# touch_board.net
KiCad netlist of a schematic drawn in EAGLE
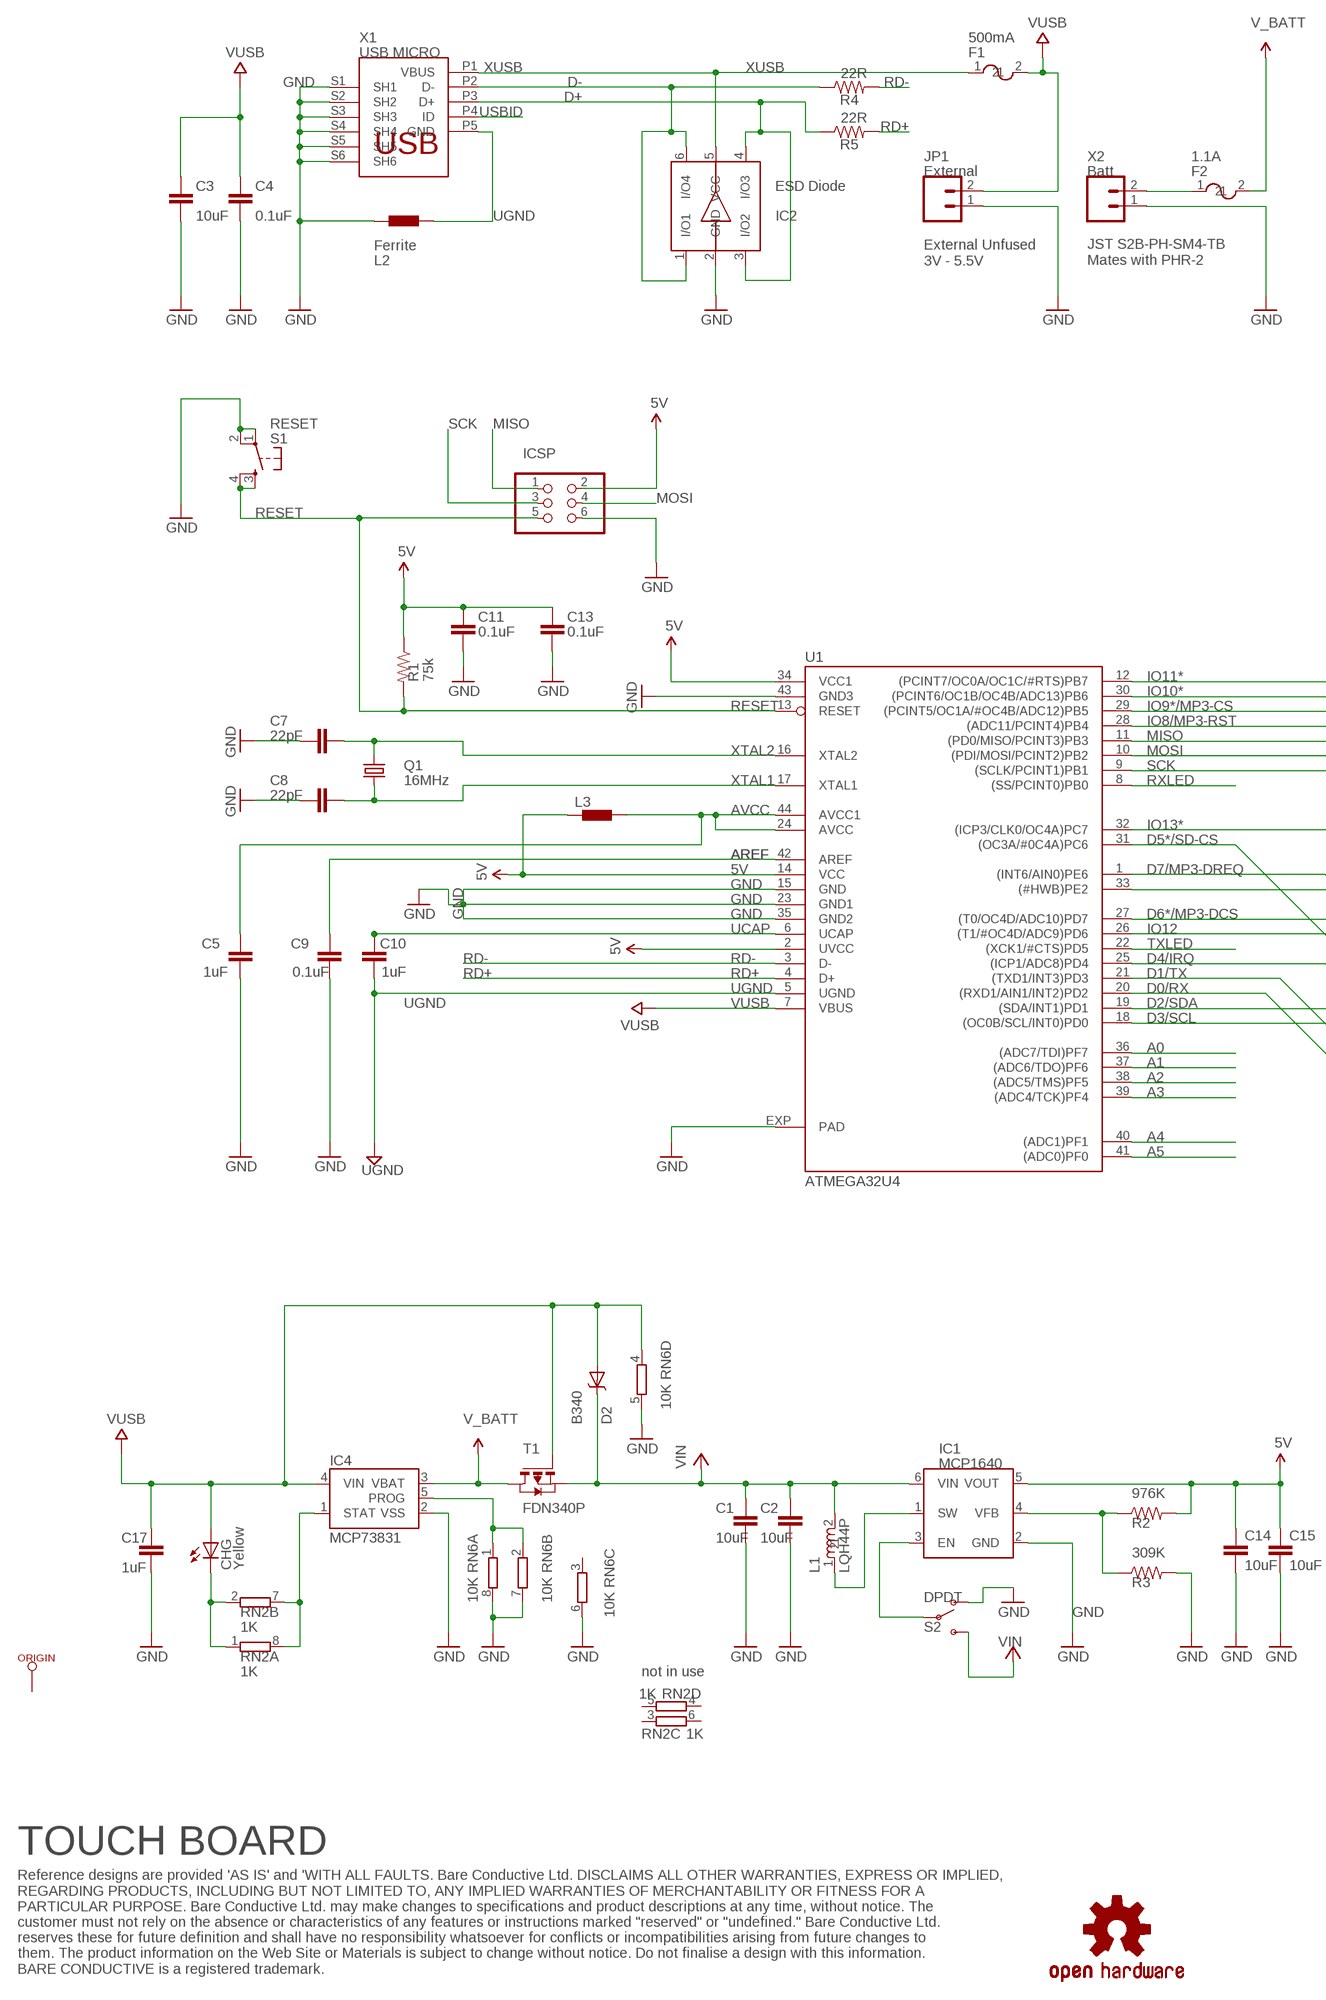
[diagram p0: schematic, sheet 1, part 1 of 2]
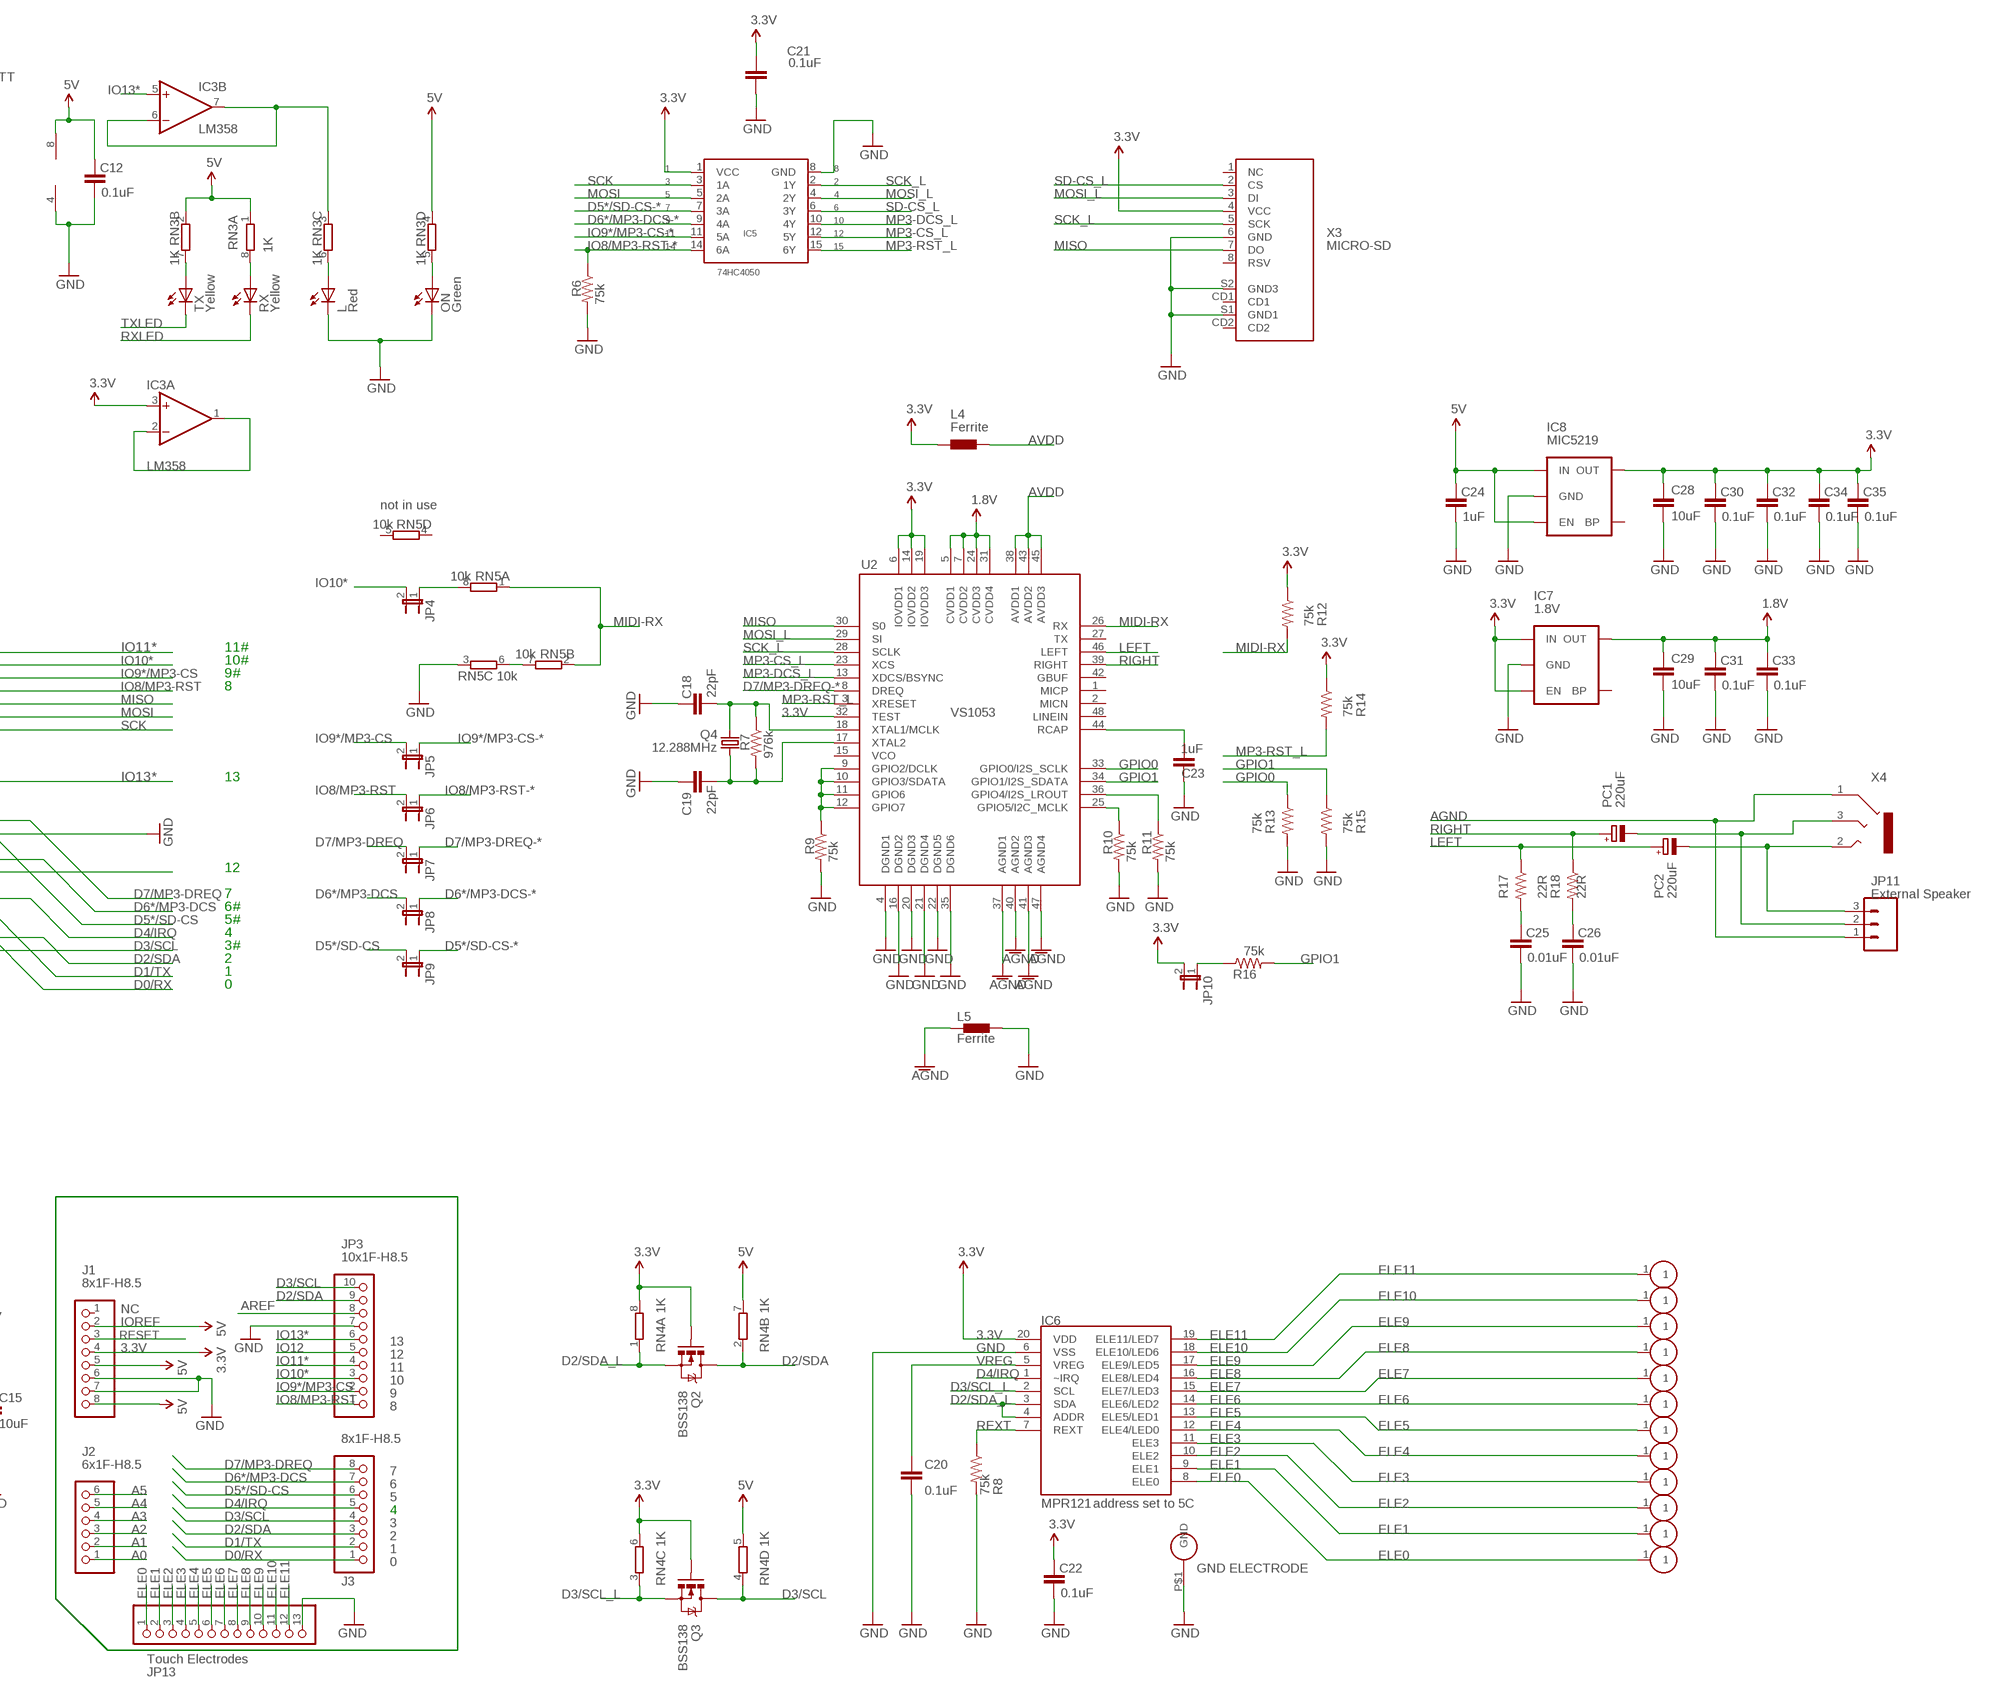
[diagram p1: schematic, sheet 1, part 2 of 2]

(export (version "E")
  (design (tool "Eeschema 10.0.6"))
  (components
    (comp (ref "C1")
      (value "10uF")
      (footprint "eagle-import:1206")
      (libsource (lib "eagle-import") (part "SparkFun-Capacitors_CAP1206"))
    )
    (comp (ref "C2")
      (value "10uF")
      (footprint "eagle-import:1206")
      (libsource (lib "eagle-import") (part "SparkFun-Capacitors_CAP1206"))
    )
    (comp (ref "C3")
      (value "10uF")
      (footprint "eagle-import:1206")
      (libsource (lib "eagle-import") (part "SparkFun-Capacitors_CAP1206"))
    )
    (comp (ref "C4")
      (value "0.1uF")
      (footprint "eagle-import:0402-CAP")
      (libsource (lib "eagle-import") (part "CAP0402-CAP"))
    )
    (comp (ref "C5")
      (value "1uF")
      (footprint "eagle-import:0402-CAP")
      (libsource (lib "eagle-import") (part "CAP0402-CAP"))
    )
    (comp (ref "C7")
      (value "22pF")
      (footprint "eagle-import:0402-CAP")
      (libsource (lib "eagle-import") (part "CAP0402-CAP"))
    )
    (comp (ref "C8")
      (value "22pF")
      (footprint "eagle-import:0402-CAP")
      (libsource (lib "eagle-import") (part "CAP0402-CAP"))
    )
    (comp (ref "C9")
      (value "0.1uF")
      (footprint "eagle-import:0402-CAP")
      (libsource (lib "eagle-import") (part "CAP0402-CAP"))
    )
    (comp (ref "C10")
      (value "1uF")
      (footprint "eagle-import:0402-CAP")
      (libsource (lib "eagle-import") (part "CAP0402-CAP"))
    )
    (comp (ref "C11")
      (value "0.1uF")
      (footprint "eagle-import:0402-CAP")
      (libsource (lib "eagle-import") (part "CAP0402-CAP"))
    )
    (comp (ref "C12")
      (value "0.1uF")
      (footprint "eagle-import:0402-CAP")
      (libsource (lib "eagle-import") (part "CAP0402-CAP"))
    )
    (comp (ref "C13")
      (value "0.1uF")
      (footprint "eagle-import:0402-CAP")
      (libsource (lib "eagle-import") (part "CAP0402-CAP"))
    )
    (comp (ref "C14")
      (value "10uF")
      (footprint "eagle-import:1206")
      (libsource (lib "eagle-import") (part "SparkFun-Capacitors_CAP1206"))
    )
    (comp (ref "C15")
      (value "10uF")
      (footprint "eagle-import:1206")
      (libsource (lib "eagle-import") (part "SparkFun-Capacitors_CAP1206"))
    )
    (comp (ref "C17")
      (value "1uF")
      (footprint "eagle-import:0402-CAP")
      (libsource (lib "eagle-import") (part "CAP0402-CAP"))
    )
    (comp (ref "C18")
      (value "22pF")
      (footprint "eagle-import:0402-CAP")
      (libsource (lib "eagle-import") (part "CAP0402-CAP"))
    )
    (comp (ref "C19")
      (value "22pF")
      (footprint "eagle-import:0402-CAP")
      (libsource (lib "eagle-import") (part "CAP0402-CAP"))
    )
    (comp (ref "C20")
      (value "0.1uF")
      (footprint "eagle-import:0402-CAP")
      (libsource (lib "eagle-import") (part "CAP0402-CAP"))
    )
    (comp (ref "C21")
      (value "0.1uF")
      (footprint "eagle-import:0402-CAP")
      (libsource (lib "eagle-import") (part "CAP0402-CAP"))
    )
    (comp (ref "C22")
      (value "0.1uF")
      (footprint "eagle-import:0402-CAP")
      (libsource (lib "eagle-import") (part "CAP0402-CAP"))
    )
    (comp (ref "C23")
      (value "1uF")
      (footprint "eagle-import:0402-CAP")
      (libsource (lib "eagle-import") (part "CAP0402-CAP"))
    )
    (comp (ref "C24")
      (value "1uF")
      (footprint "eagle-import:0402-CAP")
      (libsource (lib "eagle-import") (part "CAP0402-CAP"))
    )
    (comp (ref "C25")
      (value "0.01uF")
      (footprint "eagle-import:0402-CAP")
      (libsource (lib "eagle-import") (part "CAP0402-CAP"))
    )
    (comp (ref "C26")
      (value "0.01uF")
      (footprint "eagle-import:0402-CAP")
      (libsource (lib "eagle-import") (part "CAP0402-CAP"))
    )
    (comp (ref "C28")
      (value "10uF")
      (footprint "eagle-import:1206")
      (libsource (lib "eagle-import") (part "SparkFun-Capacitors_CAP1206"))
    )
    (comp (ref "C29")
      (value "10uF")
      (footprint "eagle-import:1206")
      (libsource (lib "eagle-import") (part "SparkFun-Capacitors_CAP1206"))
    )
    (comp (ref "C30")
      (value "0.1uF")
      (footprint "eagle-import:0402-CAP")
      (libsource (lib "eagle-import") (part "CAP0402-CAP"))
    )
    (comp (ref "C31")
      (value "0.1uF")
      (footprint "eagle-import:0402-CAP")
      (libsource (lib "eagle-import") (part "CAP0402-CAP"))
    )
    (comp (ref "C32")
      (value "0.1uF")
      (footprint "eagle-import:0402-CAP")
      (libsource (lib "eagle-import") (part "CAP0402-CAP"))
    )
    (comp (ref "C33")
      (value "0.1uF")
      (footprint "eagle-import:0402-CAP")
      (libsource (lib "eagle-import") (part "CAP0402-CAP"))
    )
    (comp (ref "C34")
      (value "0.1uF")
      (footprint "eagle-import:0402-CAP")
      (libsource (lib "eagle-import") (part "CAP0402-CAP"))
    )
    (comp (ref "C35")
      (value "0.1uF")
      (footprint "eagle-import:0402-CAP")
      (libsource (lib "eagle-import") (part "CAP0402-CAP"))
    )
    (comp (ref "CHG")
      (value "Yellow")
      (footprint "eagle-import:CHIPLED_0805")
      (libsource (lib "eagle-import") (part "LEDCHIPLED_0805"))
    )
    (comp (ref "D2")
      (value "B340")
      (footprint "eagle-import:SMA-DIODE")
      (libsource (lib "eagle-import") (part "DIODE-SCHOTTKY_"))
    )
    (comp (ref "F1")
      (value "500mA")
      (footprint "eagle-import:0805")
      (libsource (lib "eagle-import") (part "PTC"))
    )
    (comp (ref "F2")
      (value "1.1A")
      (footprint "eagle-import:0805")
      (libsource (lib "eagle-import") (part "PTC"))
    )
    (comp (ref "IC1")
      (value "MCP1640")
      (footprint "eagle-import:6-LEAD-SOT23")
      (libsource (lib "eagle-import") (part "BOOST-REG"))
    )
    (comp (ref "IC2")
      (value "ESD Diode")
      (footprint "eagle-import:SOT457")
      (libsource (lib "eagle-import") (part "PRTR5V"))
    )
    (comp (ref "IC3")
      (value "LM358")
      (footprint "eagle-import:MSOP08")
      (libsource (lib "eagle-import") (part "LMV358?MMX"))
    )
    (comp (ref "IC4")
      (value "MCP73831")
      (footprint "eagle-import:SOT23-5")
      (libsource (lib "eagle-import") (part "MCP73831"))
    )
    (comp (ref "IC5")
      (value "74HC4050")
      (footprint "eagle-import:TSSOP-16")
      (libsource (lib "eagle-import") (part "74HC4050PW"))
    )
    (comp (ref "IC6")
      (value "MPR121")
      (footprint "eagle-import:QFN-20-0.4MM")
      (libsource (lib "eagle-import") (part "MPR121QFN20"))
    )
    (comp (ref "IC7")
      (value "1.8V")
      (footprint "eagle-import:SC70")
      (libsource (lib "eagle-import") (part "V_REG_LDOSMD2"))
    )
    (comp (ref "IC8")
      (value "MIC5219")
      (footprint "eagle-import:SOT23-5")
      (libsource (lib "eagle-import") (part "V_REG_LDOSMD"))
    )
    (comp (ref "ICSP")
      (value "ICSP")
      (footprint "eagle-import:2X03")
      (libsource (lib "eagle-import") (part "PINHD-2X3"))
    )
    (comp (ref "J1")
      (value "8x1F-H8.5")
      (footprint "eagle-import:1X08")
      (libsource (lib "eagle-import") (part "PINHD-1X8"))
    )
    (comp (ref "J2")
      (value "6x1F-H8.5")
      (footprint "eagle-import:1X06")
      (libsource (lib "eagle-import") (part "PINHD-1X6"))
    )
    (comp (ref "J3")
      (value "8x1F-H8.5")
      (footprint "eagle-import:1X08")
      (libsource (lib "eagle-import") (part "PINHD-1X8"))
    )
    (comp (ref "JP1")
      (value "External")
      (footprint "eagle-import:1X02")
      (libsource (lib "eagle-import") (part "M02PTH"))
    )
    (comp (ref "JP3")
      (value "10x1F-H8.5")
      (footprint "eagle-import:1X10")
      (libsource (lib "eagle-import") (part "PINHD-1X10"))
    )
    (comp (ref "JP4")
      (value "JUMPER-2SMD-NO")
      (footprint "eagle-import:SJ_2S-NO")
      (libsource (lib "eagle-import") (part "JUMPER-2SMD-NO"))
    )
    (comp (ref "JP5")
      (value "JUMPER-2SMD-NC")
      (footprint "eagle-import:SJ_2S")
      (libsource (lib "eagle-import") (part "JUMPER-2SMD-NC"))
    )
    (comp (ref "JP6")
      (value "JUMPER-2SMD-NC")
      (footprint "eagle-import:SJ_2S")
      (libsource (lib "eagle-import") (part "JUMPER-2SMD-NC"))
    )
    (comp (ref "JP7")
      (value "JUMPER-2SMD-NC")
      (footprint "eagle-import:SJ_2S")
      (libsource (lib "eagle-import") (part "JUMPER-2SMD-NC"))
    )
    (comp (ref "JP8")
      (value "JUMPER-2SMD-NC")
      (footprint "eagle-import:SJ_2S")
      (libsource (lib "eagle-import") (part "JUMPER-2SMD-NC"))
    )
    (comp (ref "JP9")
      (value "JUMPER-2SMD-NC")
      (footprint "eagle-import:SJ_2S")
      (libsource (lib "eagle-import") (part "JUMPER-2SMD-NC"))
    )
    (comp (ref "JP10")
      (value "JUMPER-2SMD-NO")
      (footprint "eagle-import:SJ_2S-NO")
      (libsource (lib "eagle-import") (part "JUMPER-2SMD-NO"))
    )
    (comp (ref "JP11")
      (value "External Speaker")
      (footprint "eagle-import:1X03")
      (libsource (lib "eagle-import") (part "M03PTH"))
    )
    (comp (ref "JP13")
      (value "Touch Electrodes")
      (footprint "eagle-import:1X13")
      (libsource (lib "eagle-import") (part "PINHD-1X13"))
    )
    (comp (ref "L")
      (value "Red")
      (footprint "eagle-import:CHIPLED_0805")
      (libsource (lib "eagle-import") (part "LEDCHIPLED_0805"))
    )
    (comp (ref "L1")
      (value "LQH44P")
      (footprint "eagle-import:LQH44PN100MP0L")
      (libsource (lib "eagle-import") (part "LQH44P"))
    )
    (comp (ref "L2")
      (value "Ferrite")
      (footprint "eagle-import:0402")
      (libsource (lib "eagle-import") (part "BLM15HB121SN1"))
    )
    (comp (ref "L3")
      (value "BLM15HB121SN1")
      (footprint "eagle-import:0402")
      (libsource (lib "eagle-import") (part "BLM15HB121SN1"))
    )
    (comp (ref "L4")
      (value "Ferrite")
      (footprint "eagle-import:0402")
      (libsource (lib "eagle-import") (part "BLM15HB121SN1"))
    )
    (comp (ref "L5")
      (value "Ferrite")
      (footprint "eagle-import:0402")
      (libsource (lib "eagle-import") (part "BLM15HB121SN1"))
    )
    (comp (ref "ON")
      (value "Green")
      (footprint "eagle-import:CHIPLED_0805")
      (libsource (lib "eagle-import") (part "LEDCHIPLED_0805"))
    )
    (comp (ref "ORIGIN")
      (value "TP_SP")
      (footprint "eagle-import:TP-SP")
      (libsource (lib "eagle-import") (part "TP_SP"))
    )
    (comp (ref "PC1")
      (value "220uF")
      (footprint "eagle-import:PANASONIC_D")
      (libsource (lib "eagle-import") (part "CPOL-EUD"))
    )
    (comp (ref "PC2")
      (value "220uF")
      (footprint "eagle-import:PANASONIC_D")
      (libsource (lib "eagle-import") (part "CPOL-EUD"))
    )
    (comp (ref "Q1")
      (value "16MHz")
      (footprint "eagle-import:CRYSTAL-SMD-5X3")
      (libsource (lib "eagle-import") (part "CRYSTAL5X3"))
    )
    (comp (ref "Q2")
      (value "BSS138")
      (footprint "eagle-import:SOT23-3")
      (libsource (lib "eagle-import") (part "MOSFET-NCHANNELSMD"))
    )
    (comp (ref "Q3")
      (value "BSS138")
      (footprint "eagle-import:SOT23-3")
      (libsource (lib "eagle-import") (part "MOSFET-NCHANNELSMD"))
    )
    (comp (ref "Q4")
      (value "12.288MHz")
      (footprint "eagle-import:CRYSTAL-SMD-5X3")
      (libsource (lib "eagle-import") (part "CRYSTAL5X3"))
    )
    (comp (ref "R1")
      (value "75k")
      (footprint "eagle-import:0402-RES")
      (libsource (lib "eagle-import") (part "RESISTOR0402-RES"))
    )
    (comp (ref "R2")
      (value "976K")
      (footprint "eagle-import:0402-RES")
      (libsource (lib "eagle-import") (part "RESISTOR0402-RES"))
    )
    (comp (ref "R3")
      (value "309K")
      (footprint "eagle-import:0402-RES")
      (libsource (lib "eagle-import") (part "RESISTOR0402-RES"))
    )
    (comp (ref "R4")
      (value "22R")
      (footprint "eagle-import:0402-RES")
      (libsource (lib "eagle-import") (part "RESISTOR0402-RES"))
    )
    (comp (ref "R5")
      (value "22R")
      (footprint "eagle-import:0402-RES")
      (libsource (lib "eagle-import") (part "RESISTOR0402-RES"))
    )
    (comp (ref "R6")
      (value "75k")
      (footprint "eagle-import:0402-RES")
      (libsource (lib "eagle-import") (part "RESISTOR0402-RES"))
    )
    (comp (ref "R7")
      (value "976k")
      (footprint "eagle-import:0402-RES")
      (libsource (lib "eagle-import") (part "RESISTOR0402-RES"))
    )
    (comp (ref "R8")
      (value "75k")
      (footprint "eagle-import:0402-RES")
      (libsource (lib "eagle-import") (part "RESISTOR0402-RES"))
    )
    (comp (ref "R9")
      (value "75k")
      (footprint "eagle-import:0402-RES")
      (libsource (lib "eagle-import") (part "RESISTOR0402-RES"))
    )
    (comp (ref "R10")
      (value "75k")
      (footprint "eagle-import:0402-RES")
      (libsource (lib "eagle-import") (part "RESISTOR0402-RES"))
    )
    (comp (ref "R11")
      (value "75k")
      (footprint "eagle-import:0402-RES")
      (libsource (lib "eagle-import") (part "RESISTOR0402-RES"))
    )
    (comp (ref "R12")
      (value "75k")
      (footprint "eagle-import:0402-RES")
      (libsource (lib "eagle-import") (part "RESISTOR0402-RES"))
    )
    (comp (ref "R13")
      (value "75k")
      (footprint "eagle-import:0402-RES")
      (libsource (lib "eagle-import") (part "RESISTOR0402-RES"))
    )
    (comp (ref "R14")
      (value "75k")
      (footprint "eagle-import:0402-RES")
      (libsource (lib "eagle-import") (part "RESISTOR0402-RES"))
    )
    (comp (ref "R15")
      (value "75k")
      (footprint "eagle-import:0402-RES")
      (libsource (lib "eagle-import") (part "RESISTOR0402-RES"))
    )
    (comp (ref "R16")
      (value "75k")
      (footprint "eagle-import:0402-RES")
      (libsource (lib "eagle-import") (part "RESISTOR0402-RES"))
    )
    (comp (ref "R17")
      (value "22R")
      (footprint "eagle-import:0402-RES")
      (libsource (lib "eagle-import") (part "RESISTOR0402-RES"))
    )
    (comp (ref "R18")
      (value "22R")
      (footprint "eagle-import:0402-RES")
      (libsource (lib "eagle-import") (part "RESISTOR0402-RES"))
    )
    (comp (ref "RN2")
      (value "1K")
      (footprint "eagle-import:CAY16")
      (libsource (lib "eagle-import") (part "4R-NCAY16"))
    )
    (comp (ref "RN3")
      (value "1K")
      (footprint "eagle-import:CAY16")
      (libsource (lib "eagle-import") (part "4R-NCAY16"))
    )
    (comp (ref "RN4")
      (value "1K")
      (footprint "eagle-import:CAY16")
      (libsource (lib "eagle-import") (part "4R-NCAY16"))
    )
    (comp (ref "RN5")
      (value "10k")
      (footprint "eagle-import:CAY16")
      (libsource (lib "eagle-import") (part "4R-NCAY16"))
    )
    (comp (ref "RN6")
      (value "10K")
      (footprint "eagle-import:CAY16")
      (libsource (lib "eagle-import") (part "4R-NCAY16"))
    )
    (comp (ref "RX")
      (value "Yellow")
      (footprint "eagle-import:CHIPLED_0805")
      (libsource (lib "eagle-import") (part "LEDCHIPLED_0805"))
    )
    (comp (ref "S1")
      (value "RESET")
      (footprint "eagle-import:TACTILE_SWITCH_SMD@1")
      (libsource (lib "eagle-import") (part "TAC_SWITCHSND"))
    )
    (comp (ref "S2")
      (value "DPDT")
      (footprint "eagle-import:JS202011SCQN")
      (libsource (lib "eagle-import") (part "DPDT-SWITCH"))
    )
    (comp (ref "T1")
      (value "FDN340P")
      (footprint "eagle-import:SOT-23")
      (libsource (lib "eagle-import") (part "PMOSSOT23"))
    )
    (comp (ref "TX")
      (value "Yellow")
      (footprint "eagle-import:CHIPLED_0805")
      (libsource (lib "eagle-import") (part "LEDCHIPLED_0805"))
    )
    (comp (ref "U$1")
      (value "EDGE-ELEC-LEFT")
      (footprint "eagle-import:EDGE-ELEC-LEFT")
      (libsource (lib "eagle-import") (part "EDGE-ELEC-LEFT"))
    )
    (comp (ref "U$3")
      (value "EDGE-ELEC-RIGHT")
      (footprint "eagle-import:EDGE-ELEC-RIGHT")
      (libsource (lib "eagle-import") (part "EDGE-ELEC-RIGHT"))
    )
    (comp (ref "U$6")
      (value "EDGE-GND")
      (footprint "eagle-import:EDGE-GND")
      (libsource (lib "eagle-import") (part "EDGE-GND"))
    )
    (comp (ref "U$8")
      (value "OSHW-LOGO")
      (footprint "eagle-import:OSHW-LOGO")
      (libsource (lib "eagle-import") (part "OSHW-LOGO"))
    )
    (comp (ref "U$17")
      (value "EDGE-ELEC")
      (footprint "eagle-import:EDGE-ELEC")
      (libsource (lib "eagle-import") (part "EDGE-ELEC"))
    )
    (comp (ref "U$18")
      (value "EDGE-ELEC")
      (footprint "eagle-import:EDGE-ELEC")
      (libsource (lib "eagle-import") (part "EDGE-ELEC"))
    )
    (comp (ref "U$22")
      (value "EDGE-ELEC")
      (footprint "eagle-import:EDGE-ELEC")
      (libsource (lib "eagle-import") (part "EDGE-ELEC"))
    )
    (comp (ref "U$24")
      (value "EDGE-ELEC")
      (footprint "eagle-import:EDGE-ELEC")
      (libsource (lib "eagle-import") (part "EDGE-ELEC"))
    )
    (comp (ref "U$26")
      (value "EDGE-ELEC")
      (footprint "eagle-import:EDGE-ELEC")
      (libsource (lib "eagle-import") (part "EDGE-ELEC"))
    )
    (comp (ref "U$27")
      (value "EDGE-ELEC")
      (footprint "eagle-import:EDGE-ELEC")
      (libsource (lib "eagle-import") (part "EDGE-ELEC"))
    )
    (comp (ref "U$28")
      (value "EDGE-ELEC")
      (footprint "eagle-import:EDGE-ELEC")
      (libsource (lib "eagle-import") (part "EDGE-ELEC"))
    )
    (comp (ref "U$29")
      (value "EDGE-ELEC")
      (footprint "eagle-import:EDGE-ELEC")
      (libsource (lib "eagle-import") (part "EDGE-ELEC"))
    )
    (comp (ref "U$30")
      (value "EDGE-ELEC")
      (footprint "eagle-import:EDGE-ELEC")
      (libsource (lib "eagle-import") (part "EDGE-ELEC"))
    )
    (comp (ref "U$31")
      (value "EDGE-ELEC")
      (footprint "eagle-import:EDGE-ELEC")
      (libsource (lib "eagle-import") (part "EDGE-ELEC"))
    )
    (comp (ref "U1")
      (value "ATMEGA32U4")
      (footprint "eagle-import:QFN44ML7X7")
      (libsource (lib "eagle-import") (part "ATMEGA32U4-XUMU"))
    )
    (comp (ref "U2")
      (value "VS1053")
      (footprint "eagle-import:LQFP-48")
      (libsource (lib "eagle-import") (part "VS1033"))
    )
    (comp (ref "X1")
      (value "USB MICRO")
      (footprint "eagle-import:CON2_USB_MICRO_B_AT")
      (libsource (lib "eagle-import") (part "MYCON2_USB-MINI-B"))
    )
    (comp (ref "X2")
      (value "Batt")
      (footprint "eagle-import:JST-2-SMD")
      (libsource (lib "eagle-import") (part "M02-JST-2MM-SMT"))
    )
    (comp (ref "X3")
      (value "MICRO-SD")
      (footprint "eagle-import:MSDC-PP-02")
      (libsource (lib "eagle-import") (part "TOBY-SD"))
    )
    (comp (ref "X4")
      (value "SJ-3523")
      (footprint "eagle-import:3POLE-JACK")
      (libsource (lib "eagle-import") (part "SJ-3523"))
    )
  )
  (nets
    (net (code "1") (name "/A0") (class "Default")
      (node (ref "J2") (pin "1") (pinfunction "1_1") (pintype "passive"))
      (node (ref "U1") (pin "36") (pinfunction "(ADC7/TDI)PF7_36") (pintype "bidirectional"))
    )
    (net (code "2") (name "/A1") (class "Default")
      (node (ref "J2") (pin "2") (pinfunction "2_2") (pintype "passive"))
      (node (ref "U1") (pin "37") (pinfunction "(ADC6/TDO)PF6_37") (pintype "bidirectional"))
    )
    (net (code "3") (name "/A2") (class "Default")
      (node (ref "J2") (pin "3") (pinfunction "3_3") (pintype "passive"))
      (node (ref "U1") (pin "38") (pinfunction "(ADC5/TMS)PF5_38") (pintype "bidirectional"))
    )
    (net (code "4") (name "/A3") (class "Default")
      (node (ref "J2") (pin "4") (pinfunction "4_4") (pintype "passive"))
      (node (ref "U1") (pin "39") (pinfunction "(ADC4/TCK)PF4_39") (pintype "bidirectional"))
    )
    (net (code "5") (name "/A4") (class "Default")
      (node (ref "J2") (pin "5") (pinfunction "5_5") (pintype "passive"))
      (node (ref "U1") (pin "40") (pinfunction "(ADC1)PF1_40") (pintype "bidirectional"))
    )
    (net (code "6") (name "/A5") (class "Default")
      (node (ref "J2") (pin "6") (pinfunction "6_6") (pintype "passive"))
      (node (ref "U1") (pin "41") (pinfunction "(ADC0)PF0_41") (pintype "bidirectional"))
    )
    (net (code "7") (name "/AREF") (class "Default")
      (node (ref "C9") (pin "2") (pinfunction "2_2") (pintype "passive"))
      (node (ref "JP3") (pin "8") (pinfunction "8_8") (pintype "passive"))
      (node (ref "U1") (pin "42") (pinfunction "AREF_42") (pintype "power_in"))
    )
    (net (code "8") (name "/AVCC") (class "Default")
      (node (ref "C5") (pin "2") (pinfunction "2_2") (pintype "passive"))
      (node (ref "L3") (pin "2") (pinfunction "2_2") (pintype "passive"))
      (node (ref "U1") (pin "24") (pinfunction "AVCC_24") (pintype "power_in"))
      (node (ref "U1") (pin "44") (pinfunction "AVCC1_44") (pintype "power_in"))
    )
    (net (code "9") (name "/AVDD") (class "Default")
      (node (ref "L4") (pin "2") (pinfunction "2_2") (pintype "passive"))
      (node (ref "U2") (pin "38") (pinfunction "AVDD1_38") (pintype "bidirectional"))
      (node (ref "U2") (pin "43") (pinfunction "AVDD2_43") (pintype "bidirectional"))
      (node (ref "U2") (pin "45") (pinfunction "AVDD3_45") (pintype "bidirectional"))
    )
    (net (code "10") (name "/D+") (class "Default")
      (node (ref "IC2") (pin "3") (pinfunction "I/O2_3") (pintype "bidirectional"))
      (node (ref "IC2") (pin "4") (pinfunction "I/O3_4") (pintype "bidirectional"))
      (node (ref "R5") (pin "1") (pinfunction "1_1") (pintype "passive"))
      (node (ref "X1") (pin "P3") (pinfunction "D+_P3") (pintype "bidirectional"))
    )
    (net (code "11") (name "/D-") (class "Default")
      (node (ref "IC2") (pin "1") (pinfunction "I/O1_1") (pintype "bidirectional"))
      (node (ref "IC2") (pin "6") (pinfunction "I/O4_6") (pintype "bidirectional"))
      (node (ref "R4") (pin "1") (pinfunction "1_1") (pintype "passive"))
      (node (ref "X1") (pin "P2") (pinfunction "D-_P2") (pintype "bidirectional"))
    )
    (net (code "12") (name "/D0{slash}RX") (class "Default")
      (node (ref "J3") (pin "1") (pinfunction "1_1") (pintype "passive"))
      (node (ref "U1") (pin "20") (pinfunction "(RXD1/AIN1/INT2)PD2_20") (pintype "bidirectional"))
    )
    (net (code "13") (name "/D1{slash}TX") (class "Default")
      (node (ref "J3") (pin "2") (pinfunction "2_2") (pintype "passive"))
      (node (ref "U1") (pin "21") (pinfunction "(TXD1/INT3)PD3_21") (pintype "bidirectional"))
    )
    (net (code "14") (name "/D2{slash}SDA") (class "Default")
      (node (ref "J3") (pin "3") (pinfunction "3_3") (pintype "passive"))
      (node (ref "JP3") (pin "9") (pinfunction "9_9") (pintype "passive"))
      (node (ref "Q2") (pin "3") (pinfunction "D_3") (pintype "passive"))
      (node (ref "RN4") (pin "2") (pinfunction "1_2") (pintype "passive"))
      (node (ref "U1") (pin "19") (pinfunction "(SDA/INT1)PD1_19") (pintype "bidirectional"))
    )
    (net (code "15") (name "/D2{slash}SDA_L") (class "Default")
      (node (ref "IC6") (pin "3") (pinfunction "SDA_3") (pintype "bidirectional"))
      (node (ref "IC6") (pin "4") (pinfunction "ADDR_4") (pintype "bidirectional"))
      (node (ref "Q2") (pin "2") (pinfunction "S_2") (pintype "passive"))
      (node (ref "RN4") (pin "1") (pinfunction "1_1") (pintype "passive"))
    )
    (net (code "16") (name "/D3{slash}SCL") (class "Default")
      (node (ref "J3") (pin "4") (pinfunction "4_4") (pintype "passive"))
      (node (ref "JP3") (pin "10") (pinfunction "10_10") (pintype "passive"))
      (node (ref "Q3") (pin "3") (pinfunction "D_3") (pintype "passive"))
      (node (ref "RN4") (pin "4") (pinfunction "1_4") (pintype "passive"))
      (node (ref "U1") (pin "18") (pinfunction "(OC0B/SCL/INT0)PD0_18") (pintype "bidirectional"))
    )
    (net (code "17") (name "/D3{slash}SCL_L") (class "Default")
      (node (ref "IC6") (pin "2") (pinfunction "SCL_2") (pintype "bidirectional"))
      (node (ref "Q3") (pin "2") (pinfunction "S_2") (pintype "passive"))
      (node (ref "RN4") (pin "3") (pinfunction "1_3") (pintype "passive"))
    )
    (net (code "18") (name "/D4{slash}IRQ") (class "Default")
      (node (ref "IC6") (pin "1") (pinfunction "~{IRQ}_1") (pintype "bidirectional"))
      (node (ref "J3") (pin "5") (pinfunction "5_5") (pintype "passive"))
      (node (ref "U1") (pin "25") (pinfunction "(ICP1/ADC8)PD4_25") (pintype "bidirectional"))
    )
    (net (code "19") (name "/D5*{slash}SD-CS") (class "Default")
      (node (ref "J3") (pin "6") (pinfunction "6_6") (pintype "passive"))
      (node (ref "JP9") (pin "2") (pinfunction "2_2") (pintype "passive"))
      (node (ref "U1") (pin "31") (pinfunction "(OC3A/#0C4A)PC6_31") (pintype "bidirectional"))
    )
    (net (code "20") (name "/D5*{slash}SD-CS-*") (class "Default")
      (node (ref "IC5") (pin "7") (pinfunction "3A_7") (pintype "bidirectional"))
      (node (ref "JP9") (pin "1") (pinfunction "1_1") (pintype "passive"))
    )
    (net (code "21") (name "/D6*{slash}MP3-DCS") (class "Default")
      (node (ref "J3") (pin "7") (pinfunction "7_7") (pintype "passive"))
      (node (ref "JP8") (pin "2") (pinfunction "2_2") (pintype "passive"))
      (node (ref "U1") (pin "27") (pinfunction "(T0/OC4D/ADC10)PD7_27") (pintype "bidirectional"))
    )
    (net (code "22") (name "/D6*{slash}MP3-DCS-*") (class "Default")
      (node (ref "IC5") (pin "9") (pinfunction "4A_9") (pintype "bidirectional"))
      (node (ref "JP8") (pin "1") (pinfunction "1_1") (pintype "passive"))
    )
    (net (code "23") (name "/D7{slash}MP3-DREQ") (class "Default")
      (node (ref "J3") (pin "8") (pinfunction "8_8") (pintype "passive"))
      (node (ref "JP7") (pin "2") (pinfunction "2_2") (pintype "passive"))
      (node (ref "U1") (pin "1") (pinfunction "(INT6/AIN0)PE6_1") (pintype "bidirectional"))
    )
    (net (code "24") (name "/D7{slash}MP3-DREQ-*") (class "Default")
      (node (ref "JP7") (pin "1") (pinfunction "1_1") (pintype "passive"))
      (node (ref "U2") (pin "8") (pinfunction "DREQ_8") (pintype "bidirectional"))
    )
    (net (code "25") (name "/ELE0") (class "Default")
      (node (ref "IC6") (pin "8") (pinfunction "ELE0_8") (pintype "bidirectional"))
      (node (ref "JP13") (pin "1") (pinfunction "1_1") (pintype "passive"))
      (node (ref "U$1") (pin "1") (pinfunction "1_1") (pintype "bidirectional"))
    )
    (net (code "26") (name "/ELE1") (class "Default")
      (node (ref "IC6") (pin "9") (pinfunction "ELE1_9") (pintype "bidirectional"))
      (node (ref "JP13") (pin "2") (pinfunction "2_2") (pintype "passive"))
      (node (ref "U$31") (pin "1") (pinfunction "1_1") (pintype "bidirectional"))
    )
    (net (code "27") (name "/ELE2") (class "Default")
      (node (ref "IC6") (pin "10") (pinfunction "ELE2_10") (pintype "bidirectional"))
      (node (ref "JP13") (pin "3") (pinfunction "3_3") (pintype "passive"))
      (node (ref "U$30") (pin "1") (pinfunction "1_1") (pintype "bidirectional"))
    )
    (net (code "28") (name "/ELE3") (class "Default")
      (node (ref "IC6") (pin "11") (pinfunction "ELE3_11") (pintype "bidirectional"))
      (node (ref "JP13") (pin "4") (pinfunction "4_4") (pintype "passive"))
      (node (ref "U$29") (pin "1") (pinfunction "1_1") (pintype "bidirectional"))
    )
    (net (code "29") (name "/ELE4") (class "Default")
      (node (ref "IC6") (pin "12") (pinfunction "ELE4/LED0_12") (pintype "bidirectional"))
      (node (ref "JP13") (pin "5") (pinfunction "5_5") (pintype "passive"))
      (node (ref "U$28") (pin "1") (pinfunction "1_1") (pintype "bidirectional"))
    )
    (net (code "30") (name "/ELE5") (class "Default")
      (node (ref "IC6") (pin "13") (pinfunction "ELE5/LED1_13") (pintype "bidirectional"))
      (node (ref "JP13") (pin "6") (pinfunction "6_6") (pintype "passive"))
      (node (ref "U$27") (pin "1") (pinfunction "1_1") (pintype "bidirectional"))
    )
    (net (code "31") (name "/ELE6") (class "Default")
      (node (ref "IC6") (pin "14") (pinfunction "ELE6/LED2_14") (pintype "bidirectional"))
      (node (ref "JP13") (pin "7") (pinfunction "7_7") (pintype "passive"))
      (node (ref "U$26") (pin "1") (pinfunction "1_1") (pintype "bidirectional"))
    )
    (net (code "32") (name "/ELE7") (class "Default")
      (node (ref "IC6") (pin "15") (pinfunction "ELE7/LED3_15") (pintype "bidirectional"))
      (node (ref "JP13") (pin "8") (pinfunction "8_8") (pintype "passive"))
      (node (ref "U$24") (pin "1") (pinfunction "1_1") (pintype "bidirectional"))
    )
    (net (code "33") (name "/ELE8") (class "Default")
      (node (ref "IC6") (pin "16") (pinfunction "ELE8/LED4_16") (pintype "bidirectional"))
      (node (ref "JP13") (pin "9") (pinfunction "9_9") (pintype "passive"))
      (node (ref "U$22") (pin "1") (pinfunction "1_1") (pintype "bidirectional"))
    )
    (net (code "34") (name "/ELE9") (class "Default")
      (node (ref "IC6") (pin "17") (pinfunction "ELE9/LED5_17") (pintype "bidirectional"))
      (node (ref "JP13") (pin "10") (pinfunction "10_10") (pintype "passive"))
      (node (ref "U$18") (pin "1") (pinfunction "1_1") (pintype "bidirectional"))
    )
    (net (code "35") (name "/ELE10") (class "Default")
      (node (ref "IC6") (pin "18") (pinfunction "ELE10/LED6_18") (pintype "bidirectional"))
      (node (ref "JP13") (pin "11") (pinfunction "11_11") (pintype "passive"))
      (node (ref "U$17") (pin "1") (pinfunction "1_1") (pintype "bidirectional"))
    )
    (net (code "36") (name "/ELE11") (class "Default")
      (node (ref "IC6") (pin "19") (pinfunction "ELE11/LED7_19") (pintype "bidirectional"))
      (node (ref "JP13") (pin "12") (pinfunction "12_12") (pintype "passive"))
      (node (ref "U$3") (pin "1") (pinfunction "1_1") (pintype "bidirectional"))
    )
    (net (code "37") (name "/GPIO0") (class "Default")
      (node (ref "R13") (pin "1") (pinfunction "1_1") (pintype "passive"))
      (node (ref "U2") (pin "33") (pinfunction "GPIO0/I2S_SCLK_33") (pintype "bidirectional"))
    )
    (net (code "38") (name "/GPIO1") (class "Default")
      (node (ref "R15") (pin "1") (pinfunction "1_1") (pintype "passive"))
      (node (ref "R16") (pin "2") (pinfunction "2_2") (pintype "passive"))
      (node (ref "U2") (pin "34") (pinfunction "GPIO1/I2S_SDATA_34") (pintype "bidirectional"))
    )
    (net (code "39") (name "/IO8{slash}MP3-RST") (class "Default")
      (node (ref "JP3") (pin "1") (pinfunction "1_1") (pintype "passive"))
      (node (ref "JP6") (pin "2") (pinfunction "2_2") (pintype "passive"))
      (node (ref "U1") (pin "28") (pinfunction "(ADC11/PCINT4)PB4_28") (pintype "bidirectional"))
    )
    (net (code "40") (name "/IO8{slash}MP3-RST-*") (class "Default")
      (node (ref "IC5") (pin "14") (pinfunction "6A_14") (pintype "bidirectional"))
      (node (ref "JP6") (pin "1") (pinfunction "1_1") (pintype "passive"))
      (node (ref "R6") (pin "1") (pinfunction "1_1") (pintype "passive"))
    )
    (net (code "41") (name "/IO9*{slash}MP3-CS") (class "Default")
      (node (ref "JP3") (pin "2") (pinfunction "2_2") (pintype "passive"))
      (node (ref "JP5") (pin "2") (pinfunction "2_2") (pintype "passive"))
      (node (ref "U1") (pin "29") (pinfunction "(PCINT5/OC1A/#OC4B/ADC12)PB5_29") (pintype "bidirectional"))
    )
    (net (code "42") (name "/IO9*{slash}MP3-CS-*") (class "Default")
      (node (ref "IC5") (pin "11") (pinfunction "5A_11") (pintype "bidirectional"))
      (node (ref "JP5") (pin "1") (pinfunction "1_1") (pintype "passive"))
    )
    (net (code "43") (name "/IO10*") (class "Default")
      (node (ref "JP3") (pin "3") (pinfunction "3_3") (pintype "passive"))
      (node (ref "JP4") (pin "2") (pinfunction "2_2") (pintype "passive"))
      (node (ref "U1") (pin "30") (pinfunction "(PCINT6/OC1B/OC4B/ADC13)PB6_30") (pintype "bidirectional"))
    )
    (net (code "44") (name "/IO11*") (class "Default")
      (node (ref "JP3") (pin "4") (pinfunction "4_4") (pintype "passive"))
      (node (ref "U1") (pin "12") (pinfunction "(PCINT7/OC0A/OC1C/#RTS)PB7_12") (pintype "bidirectional"))
    )
    (net (code "45") (name "/IO12") (class "Default")
      (node (ref "JP3") (pin "5") (pinfunction "5_5") (pintype "passive"))
      (node (ref "U1") (pin "26") (pinfunction "(T1/#OC4D/ADC9)PD6_26") (pintype "bidirectional"))
    )
    (net (code "46") (name "/IO13*") (class "Default")
      (node (ref "IC3") (pin "5") (pinfunction "+IN_5") (pintype "input"))
      (node (ref "JP3") (pin "6") (pinfunction "6_6") (pintype "passive"))
      (node (ref "U1") (pin "32") (pinfunction "(ICP3/CLK0/OC4A)PC7_32") (pintype "bidirectional"))
    )
    (net (code "47") (name "/LEFT") (class "Default")
      (node (ref "PC2") (pin "+") (pinfunction "+_+") (pintype "passive"))
      (node (ref "R17") (pin "1") (pinfunction "1_1") (pintype "passive"))
      (node (ref "U2") (pin "46") (pinfunction "LEFT_46") (pintype "bidirectional"))
    )
    (net (code "48") (name "/MIDI-RX") (class "Default")
      (node (ref "R12") (pin "2") (pinfunction "2_2") (pintype "passive"))
      (node (ref "RN5") (pin "1") (pinfunction "1_1") (pintype "passive"))
      (node (ref "RN5") (pin "2") (pinfunction "1_2") (pintype "passive"))
      (node (ref "U2") (pin "26") (pinfunction "RX_26") (pintype "bidirectional"))
    )
    (net (code "49") (name "/MISO") (class "Default")
      (node (ref "ICSP") (pin "1") (pinfunction "1_1") (pintype "passive"))
      (node (ref "U1") (pin "11") (pinfunction "(PD0/MISO/PCINT3)PB3_11") (pintype "bidirectional"))
      (node (ref "U2") (pin "30") (pinfunction "S0_30") (pintype "bidirectional"))
      (node (ref "X3") (pin "7") (pinfunction "DO_7") (pintype "bidirectional"))
    )
    (net (code "50") (name "/MOSI") (class "Default")
      (node (ref "IC5") (pin "5") (pinfunction "2A_5") (pintype "bidirectional"))
      (node (ref "ICSP") (pin "4") (pinfunction "4_4") (pintype "passive"))
      (node (ref "U1") (pin "10") (pinfunction "(PDI/MOSI/PCINT2)PB2_10") (pintype "bidirectional"))
    )
    (net (code "51") (name "/MOSI_L") (class "Default")
      (node (ref "IC5") (pin "4") (pinfunction "2Y_4") (pintype "bidirectional"))
      (node (ref "U2") (pin "29") (pinfunction "SI_29") (pintype "bidirectional"))
      (node (ref "X3") (pin "3") (pinfunction "DI_3") (pintype "bidirectional"))
    )
    (net (code "52") (name "/MP3-CS_L") (class "Default")
      (node (ref "IC5") (pin "12") (pinfunction "5Y_12") (pintype "bidirectional"))
      (node (ref "U2") (pin "23") (pinfunction "XCS_23") (pintype "bidirectional"))
    )
    (net (code "53") (name "/MP3-DCS_L") (class "Default")
      (node (ref "IC5") (pin "10") (pinfunction "4Y_10") (pintype "bidirectional"))
      (node (ref "U2") (pin "13") (pinfunction "XDCS/BSYNC_13") (pintype "bidirectional"))
    )
    (net (code "54") (name "/MP3-RST_L") (class "Default")
      (node (ref "IC5") (pin "15") (pinfunction "6Y_15") (pintype "bidirectional"))
      (node (ref "R14") (pin "2") (pinfunction "2_2") (pintype "passive"))
      (node (ref "U2") (pin "3") (pinfunction "XRESET_3") (pintype "bidirectional"))
    )
    (net (code "55") (name "/RD+") (class "Default")
      (node (ref "R5") (pin "2") (pinfunction "2_2") (pintype "passive"))
      (node (ref "U1") (pin "4") (pinfunction "D+_4") (pintype "bidirectional"))
    )
    (net (code "56") (name "/RD-") (class "Default")
      (node (ref "R4") (pin "2") (pinfunction "2_2") (pintype "passive"))
      (node (ref "U1") (pin "3") (pinfunction "D-_3") (pintype "bidirectional"))
    )
    (net (code "57") (name "/RESET") (class "Default")
      (node (ref "ICSP") (pin "5") (pinfunction "5_5") (pintype "passive"))
      (node (ref "J1") (pin "3") (pinfunction "3_3") (pintype "passive"))
      (node (ref "R1") (pin "2") (pinfunction "2_2") (pintype "passive"))
      (node (ref "S1") (pin "3") (pinfunction "3_3") (pintype "passive"))
      (node (ref "S1") (pin "4") (pinfunction "4_4") (pintype "passive"))
      (node (ref "U1") (pin "13") (pinfunction "RESET_13") (pintype "input"))
    )
    (net (code "58") (name "/REXT") (class "Default")
      (node (ref "IC6") (pin "7") (pinfunction "REXT_7") (pintype "bidirectional"))
      (node (ref "R8") (pin "1") (pinfunction "1_1") (pintype "passive"))
    )
    (net (code "59") (name "/RIGHT") (class "Default")
      (node (ref "PC1") (pin "+") (pinfunction "+_+") (pintype "passive"))
      (node (ref "R18") (pin "1") (pinfunction "1_1") (pintype "passive"))
      (node (ref "U2") (pin "39") (pinfunction "RIGHT_39") (pintype "bidirectional"))
    )
    (net (code "60") (name "/RXLED") (class "Default")
      (node (ref "RX") (pin "C") (pinfunction "C_C") (pintype "passive"))
      (node (ref "U1") (pin "8") (pinfunction "(SS/PCINT0)PB0_8") (pintype "bidirectional"))
    )
    (net (code "61") (name "/SCK") (class "Default")
      (node (ref "IC5") (pin "3") (pinfunction "1A_3") (pintype "bidirectional"))
      (node (ref "ICSP") (pin "3") (pinfunction "3_3") (pintype "passive"))
      (node (ref "U1") (pin "9") (pinfunction "(SCLK/PCINT1)PB1_9") (pintype "bidirectional"))
    )
    (net (code "62") (name "/SCK_L") (class "Default")
      (node (ref "IC5") (pin "2") (pinfunction "1Y_2") (pintype "bidirectional"))
      (node (ref "U2") (pin "28") (pinfunction "SCLK_28") (pintype "bidirectional"))
      (node (ref "X3") (pin "5") (pinfunction "SCK_5") (pintype "bidirectional"))
    )
    (net (code "63") (name "/SD-CS_L") (class "Default")
      (node (ref "IC5") (pin "6") (pinfunction "3Y_6") (pintype "bidirectional"))
      (node (ref "X3") (pin "2") (pinfunction "CS_2") (pintype "bidirectional"))
    )
    (net (code "64") (name "/TXLED") (class "Default")
      (node (ref "TX") (pin "C") (pinfunction "C_C") (pintype "passive"))
      (node (ref "U1") (pin "22") (pinfunction "(XCK1/#CTS)PD5_22") (pintype "bidirectional"))
    )
    (net (code "65") (name "/UCAP") (class "Default")
      (node (ref "C10") (pin "2") (pinfunction "2_2") (pintype "passive"))
      (node (ref "U1") (pin "6") (pinfunction "UCAP_6") (pintype "passive"))
    )
    (net (code "66") (name "/USBID") (class "Default")
      (node (ref "X1") (pin "P4") (pinfunction "ID_P4") (pintype "bidirectional"))
    )
    (net (code "67") (name "/VREG") (class "Default")
      (node (ref "C20") (pin "2") (pinfunction "2_2") (pintype "passive"))
      (node (ref "IC6") (pin "5") (pinfunction "VREG_5") (pintype "bidirectional"))
    )
    (net (code "68") (name "/XTAL1") (class "Default")
      (node (ref "C8") (pin "1") (pinfunction "1_1") (pintype "passive"))
      (node (ref "Q1") (pin "1") (pinfunction "1_1") (pintype "passive"))
      (node (ref "U1") (pin "17") (pinfunction "XTAL1_17") (pintype "bidirectional"))
    )
    (net (code "69") (name "/XTAL2") (class "Default")
      (node (ref "C7") (pin "1") (pinfunction "1_1") (pintype "passive"))
      (node (ref "Q1") (pin "3") (pinfunction "2_3") (pintype "passive"))
      (node (ref "U1") (pin "16") (pinfunction "XTAL2_16") (pintype "bidirectional"))
    )
    (net (code "70") (name "/XUSB") (class "Default")
      (node (ref "F1") (pin "1") (pinfunction "1_1") (pintype "bidirectional"))
      (node (ref "IC2") (pin "5") (pinfunction "VCC_5") (pintype "bidirectional"))
      (node (ref "X1") (pin "P1") (pinfunction "VBUS_P1") (pintype "power_in"))
    )
    (net (code "71") (name "1.8V") (class "Default")
      (node (ref "C29") (pin "1") (pinfunction "1_1") (pintype "passive"))
      (node (ref "C31") (pin "2") (pinfunction "2_2") (pintype "passive"))
      (node (ref "C33") (pin "2") (pinfunction "2_2") (pintype "passive"))
      (node (ref "IC7") (pin "5") (pinfunction "OUT_5") (pintype "passive"))
      (node (ref "U2") (pin "24") (pinfunction "CVDD3_24") (pintype "bidirectional"))
      (node (ref "U2") (pin "31") (pinfunction "CVDD4_31") (pintype "bidirectional"))
      (node (ref "U2") (pin "5") (pinfunction "CVDD1_5") (pintype "bidirectional"))
      (node (ref "U2") (pin "7") (pinfunction "CVDD2_7") (pintype "bidirectional"))
    )
    (net (code "72") (name "3.3V") (class "Default")
      (node (ref "C21") (pin "2") (pinfunction "2_2") (pintype "passive"))
      (node (ref "C22") (pin "2") (pinfunction "2_2") (pintype "passive"))
      (node (ref "C28") (pin "1") (pinfunction "1_1") (pintype "passive"))
      (node (ref "C30") (pin "2") (pinfunction "2_2") (pintype "passive"))
      (node (ref "C32") (pin "2") (pinfunction "2_2") (pintype "passive"))
      (node (ref "C34") (pin "2") (pinfunction "2_2") (pintype "passive"))
      (node (ref "C35") (pin "2") (pinfunction "2_2") (pintype "passive"))
      (node (ref "IC3") (pin "3") (pinfunction "+IN_3") (pintype "input"))
      (node (ref "IC5") (pin "1") (pinfunction "VCC_1") (pintype "bidirectional"))
      (node (ref "IC6") (pin "20") (pinfunction "VDD_20") (pintype "bidirectional"))
      (node (ref "IC7") (pin "1") (pinfunction "IN_1") (pintype "input"))
      (node (ref "IC7") (pin "3") (pinfunction "EN_3") (pintype "input"))
      (node (ref "IC8") (pin "5") (pinfunction "OUT_5") (pintype "passive"))
      (node (ref "J1") (pin "4") (pinfunction "4_4") (pintype "passive"))
      (node (ref "JP10") (pin "2") (pinfunction "2_2") (pintype "passive"))
      (node (ref "L4") (pin "1") (pinfunction "1_1") (pintype "passive"))
      (node (ref "Q2") (pin "1") (pinfunction "G_1") (pintype "passive"))
      (node (ref "Q3") (pin "1") (pinfunction "G_1") (pintype "passive"))
      (node (ref "R12") (pin "1") (pinfunction "1_1") (pintype "passive"))
      (node (ref "R14") (pin "1") (pinfunction "1_1") (pintype "passive"))
      (node (ref "RN4") (pin "6") (pinfunction "2_6") (pintype "passive"))
      (node (ref "RN4") (pin "8") (pinfunction "2_8") (pintype "passive"))
      (node (ref "U2") (pin "14") (pinfunction "IOVDD2_14") (pintype "bidirectional"))
      (node (ref "U2") (pin "19") (pinfunction "IOVDD3_19") (pintype "bidirectional"))
      (node (ref "U2") (pin "32") (pinfunction "TEST_32") (pintype "bidirectional"))
      (node (ref "U2") (pin "6") (pinfunction "IOVDD1_6") (pintype "bidirectional"))
      (node (ref "X3") (pin "4") (pinfunction "VCC_4") (pintype "bidirectional"))
    )
    (net (code "73") (name "5V") (class "Default")
      (node (ref "C11") (pin "2") (pinfunction "2_2") (pintype "passive"))
      (node (ref "C12") (pin "2") (pinfunction "2_2") (pintype "passive"))
      (node (ref "C13") (pin "2") (pinfunction "2_2") (pintype "passive"))
      (node (ref "C14") (pin "1") (pinfunction "1_1") (pintype "passive"))
      (node (ref "C15") (pin "1") (pinfunction "1_1") (pintype "passive"))
      (node (ref "C24") (pin "2") (pinfunction "2_2") (pintype "passive"))
      (node (ref "IC1") (pin "5") (pinfunction "VOUT_5") (pintype "bidirectional"))
      (node (ref "IC3") (pin "8") (pinfunction "V+_8") (pintype "power_in"))
      (node (ref "IC8") (pin "1") (pinfunction "IN_1") (pintype "input"))
      (node (ref "IC8") (pin "3") (pinfunction "EN_3") (pintype "input"))
      (node (ref "ICSP") (pin "2") (pinfunction "2_2") (pintype "passive"))
      (node (ref "J1") (pin "2") (pinfunction "2_2") (pintype "passive"))
      (node (ref "J1") (pin "5") (pinfunction "5_5") (pintype "passive"))
      (node (ref "J1") (pin "8") (pinfunction "8_8") (pintype "passive"))
      (node (ref "L3") (pin "1") (pinfunction "1_1") (pintype "passive"))
      (node (ref "R1") (pin "1") (pinfunction "1_1") (pintype "passive"))
      (node (ref "R2") (pin "2") (pinfunction "2_2") (pintype "passive"))
      (node (ref "RN3") (pin "1") (pinfunction "1_1") (pintype "passive"))
      (node (ref "RN3") (pin "2") (pinfunction "1_2") (pintype "passive"))
      (node (ref "RN3") (pin "4") (pinfunction "1_4") (pintype "passive"))
      (node (ref "RN4") (pin "5") (pinfunction "2_5") (pintype "passive"))
      (node (ref "RN4") (pin "7") (pinfunction "2_7") (pintype "passive"))
      (node (ref "U1") (pin "14") (pinfunction "VCC_14") (pintype "power_in"))
      (node (ref "U1") (pin "2") (pinfunction "UVCC_2") (pintype "power_in"))
      (node (ref "U1") (pin "34") (pinfunction "VCC1_34") (pintype "power_in"))
    )
    (net (code "74") (name "AGND") (class "Default")
      (node (ref "JP11") (pin "1") (pinfunction "1_1") (pintype "passive"))
      (node (ref "L5") (pin "1") (pinfunction "1_1") (pintype "passive"))
      (node (ref "U2") (pin "37") (pinfunction "AGND1_37") (pintype "bidirectional"))
      (node (ref "U2") (pin "40") (pinfunction "AGND2_40") (pintype "bidirectional"))
      (node (ref "U2") (pin "41") (pinfunction "AGND3_41") (pintype "bidirectional"))
      (node (ref "U2") (pin "47") (pinfunction "AGND4_47") (pintype "bidirectional"))
      (node (ref "X4") (pin "1") (pinfunction "1_1") (pintype "passive"))
    )
    (net (code "75") (name "GND") (class "Default")
      (node (ref "C1") (pin "2") (pinfunction "2_2") (pintype "passive"))
      (node (ref "C11") (pin "1") (pinfunction "1_1") (pintype "passive"))
      (node (ref "C12") (pin "1") (pinfunction "1_1") (pintype "passive"))
      (node (ref "C13") (pin "1") (pinfunction "1_1") (pintype "passive"))
      (node (ref "C14") (pin "2") (pinfunction "2_2") (pintype "passive"))
      (node (ref "C15") (pin "2") (pinfunction "2_2") (pintype "passive"))
      (node (ref "C17") (pin "1") (pinfunction "1_1") (pintype "passive"))
      (node (ref "C18") (pin "2") (pinfunction "2_2") (pintype "passive"))
      (node (ref "C19") (pin "2") (pinfunction "2_2") (pintype "passive"))
      (node (ref "C2") (pin "2") (pinfunction "2_2") (pintype "passive"))
      (node (ref "C20") (pin "1") (pinfunction "1_1") (pintype "passive"))
      (node (ref "C21") (pin "1") (pinfunction "1_1") (pintype "passive"))
      (node (ref "C22") (pin "1") (pinfunction "1_1") (pintype "passive"))
      (node (ref "C23") (pin "2") (pinfunction "2_2") (pintype "passive"))
      (node (ref "C24") (pin "1") (pinfunction "1_1") (pintype "passive"))
      (node (ref "C25") (pin "1") (pinfunction "1_1") (pintype "passive"))
      (node (ref "C26") (pin "1") (pinfunction "1_1") (pintype "passive"))
      (node (ref "C28") (pin "2") (pinfunction "2_2") (pintype "passive"))
      (node (ref "C29") (pin "2") (pinfunction "2_2") (pintype "passive"))
      (node (ref "C3") (pin "2") (pinfunction "2_2") (pintype "passive"))
      (node (ref "C30") (pin "1") (pinfunction "1_1") (pintype "passive"))
      (node (ref "C31") (pin "1") (pinfunction "1_1") (pintype "passive"))
      (node (ref "C32") (pin "1") (pinfunction "1_1") (pintype "passive"))
      (node (ref "C33") (pin "1") (pinfunction "1_1") (pintype "passive"))
      (node (ref "C34") (pin "1") (pinfunction "1_1") (pintype "passive"))
      (node (ref "C35") (pin "1") (pinfunction "1_1") (pintype "passive"))
      (node (ref "C4") (pin "1") (pinfunction "1_1") (pintype "passive"))
      (node (ref "C5") (pin "1") (pinfunction "1_1") (pintype "passive"))
      (node (ref "C7") (pin "2") (pinfunction "2_2") (pintype "passive"))
      (node (ref "C8") (pin "2") (pinfunction "2_2") (pintype "passive"))
      (node (ref "C9") (pin "1") (pinfunction "1_1") (pintype "passive"))
      (node (ref "IC1") (pin "2") (pinfunction "GND_2") (pintype "bidirectional"))
      (node (ref "IC2") (pin "2") (pinfunction "GND_2") (pintype "bidirectional"))
      (node (ref "IC3") (pin "4") (pinfunction "V-_4") (pintype "power_in"))
      (node (ref "IC4") (pin "2") (pinfunction "VSS_2") (pintype "power_in"))
      (node (ref "IC5") (pin "8") (pinfunction "GND_8") (pintype "bidirectional"))
      (node (ref "IC6") (pin "6") (pinfunction "VSS_6") (pintype "bidirectional"))
      (node (ref "IC7") (pin "2") (pinfunction "GND_2") (pintype "input"))
      (node (ref "IC8") (pin "2") (pinfunction "GND_2") (pintype "input"))
      (node (ref "ICSP") (pin "6") (pinfunction "6_6") (pintype "passive"))
      (node (ref "J1") (pin "6") (pinfunction "6_6") (pintype "passive"))
      (node (ref "J1") (pin "7") (pinfunction "7_7") (pintype "passive"))
      (node (ref "JP1") (pin "1") (pinfunction "1_1") (pintype "passive"))
      (node (ref "JP13") (pin "13") (pinfunction "13_13") (pintype "passive"))
      (node (ref "JP3") (pin "7") (pinfunction "7_7") (pintype "passive"))
      (node (ref "L") (pin "C") (pinfunction "C_C") (pintype "passive"))
      (node (ref "L2") (pin "1") (pinfunction "1_1") (pintype "passive"))
      (node (ref "L5") (pin "2") (pinfunction "2_2") (pintype "passive"))
      (node (ref "ON") (pin "C") (pinfunction "C_C") (pintype "passive"))
      (node (ref "R10") (pin "2") (pinfunction "2_2") (pintype "passive"))
      (node (ref "R11") (pin "2") (pinfunction "2_2") (pintype "passive"))
      (node (ref "R13") (pin "2") (pinfunction "2_2") (pintype "passive"))
      (node (ref "R15") (pin "2") (pinfunction "2_2") (pintype "passive"))
      (node (ref "R3") (pin "2") (pinfunction "2_2") (pintype "passive"))
      (node (ref "R6") (pin "2") (pinfunction "2_2") (pintype "passive"))
      (node (ref "R8") (pin "2") (pinfunction "2_2") (pintype "passive"))
      (node (ref "R9") (pin "2") (pinfunction "2_2") (pintype "passive"))
      (node (ref "RN5") (pin "3") (pinfunction "1_3") (pintype "passive"))
      (node (ref "RN6") (pin "5") (pinfunction "2_5") (pintype "passive"))
      (node (ref "RN6") (pin "6") (pinfunction "2_6") (pintype "passive"))
      (node (ref "RN6") (pin "7") (pinfunction "2_7") (pintype "passive"))
      (node (ref "RN6") (pin "8") (pinfunction "2_8") (pintype "passive"))
      (node (ref "S1") (pin "1") (pinfunction "1_1") (pintype "passive"))
      (node (ref "S1") (pin "2") (pinfunction "2_2") (pintype "passive"))
      (node (ref "S2") (pin "4") (pinfunction "4_4") (pintype "passive"))
      (node (ref "U$6") (pin "P$1") (pinfunction "GND_P$1") (pintype "bidirectional"))
      (node (ref "U1") (pin "15") (pinfunction "GND_15") (pintype "power_in"))
      (node (ref "U1") (pin "23") (pinfunction "GND1_23") (pintype "power_in"))
      (node (ref "U1") (pin "33") (pinfunction "(#HWB)PE2_33") (pintype "bidirectional"))
      (node (ref "U1") (pin "35") (pinfunction "GND2_35") (pintype "power_in"))
      (node (ref "U1") (pin "43") (pinfunction "GND3_43") (pintype "power_in"))
      (node (ref "U1") (pin "EXP") (pinfunction "PAD_EXP") (pintype "power_in"))
      (node (ref "U2") (pin "16") (pinfunction "DGND2_16") (pintype "bidirectional"))
      (node (ref "U2") (pin "20") (pinfunction "DGND3_20") (pintype "bidirectional"))
      (node (ref "U2") (pin "21") (pinfunction "DGND4_21") (pintype "bidirectional"))
      (node (ref "U2") (pin "22") (pinfunction "DGND5_22") (pintype "bidirectional"))
      (node (ref "U2") (pin "35") (pinfunction "DGND6_35") (pintype "bidirectional"))
      (node (ref "U2") (pin "4") (pinfunction "DGND1_4") (pintype "bidirectional"))
      (node (ref "X1") (pin "S1") (pinfunction "SH1_S1") (pintype "passive"))
      (node (ref "X1") (pin "S2") (pinfunction "SH2_S2") (pintype "passive"))
      (node (ref "X1") (pin "S3") (pinfunction "SH3_S3") (pintype "passive"))
      (node (ref "X1") (pin "S4") (pinfunction "SH4_S4") (pintype "passive"))
      (node (ref "X1") (pin "S5") (pinfunction "SH5_S5") (pintype "passive"))
      (node (ref "X1") (pin "S6") (pinfunction "SH6_S6") (pintype "passive"))
      (node (ref "X2") (pin "1") (pinfunction "1_1") (pintype "passive"))
      (node (ref "X3") (pin "6") (pinfunction "GND_6") (pintype "bidirectional"))
      (node (ref "X3") (pin "S1") (pinfunction "GND1_S1") (pintype "bidirectional"))
      (node (ref "X3") (pin "S2") (pinfunction "GND3_S2") (pintype "bidirectional"))
    )
    (net (code "76") (name "Net-(C25-Pad2)") (class "Default")
      (node (ref "C25") (pin "2") (pinfunction "2_2") (pintype "passive"))
      (node (ref "R17") (pin "2") (pinfunction "2_2") (pintype "passive"))
    )
    (net (code "77") (name "Net-(C26-Pad2)") (class "Default")
      (node (ref "C26") (pin "2") (pinfunction "2_2") (pintype "passive"))
      (node (ref "R18") (pin "2") (pinfunction "2_2") (pintype "passive"))
    )
    (net (code "78") (name "Net-(F2-Pad1)") (class "Default")
      (node (ref "F2") (pin "1") (pinfunction "1_1") (pintype "bidirectional"))
      (node (ref "X2") (pin "2") (pinfunction "2_2") (pintype "passive"))
    )
    (net (code "79") (name "Net-(IC1-EN)") (class "Default")
      (node (ref "IC1") (pin "3") (pinfunction "EN_3") (pintype "bidirectional"))
      (node (ref "S2") (pin "5") (pinfunction "5_5") (pintype "passive"))
    )
    (net (code "80") (name "Net-(IC1-SW)") (class "Default")
      (node (ref "IC1") (pin "1") (pinfunction "SW_1") (pintype "bidirectional"))
      (node (ref "L1") (pin "1") (pinfunction "1_1") (pintype "bidirectional"))
    )
    (net (code "81") (name "Net-(IC1-VFB)") (class "Default")
      (node (ref "IC1") (pin "4") (pinfunction "VFB_4") (pintype "bidirectional"))
      (node (ref "R2") (pin "1") (pinfunction "1_1") (pintype "passive"))
      (node (ref "R3") (pin "1") (pinfunction "1_1") (pintype "passive"))
    )
    (net (code "82") (name "Net-(IC3A--IN)") (class "Default")
      (node (ref "IC3") (pin "1") (pinfunction "OUT_1") (pintype "output"))
      (node (ref "IC3") (pin "2") (pinfunction "-IN_2") (pintype "input"))
    )
    (net (code "83") (name "Net-(IC3B--IN)") (class "Default")
      (node (ref "IC3") (pin "6") (pinfunction "-IN_6") (pintype "input"))
      (node (ref "IC3") (pin "7") (pinfunction "OUT_7") (pintype "output"))
      (node (ref "RN3") (pin "3") (pinfunction "1_3") (pintype "passive"))
    )
    (net (code "84") (name "Net-(IC4-PROG)") (class "Default")
      (node (ref "IC4") (pin "5") (pinfunction "PROG_5") (pintype "input"))
      (node (ref "RN6") (pin "1") (pinfunction "1_1") (pintype "passive"))
      (node (ref "RN6") (pin "2") (pinfunction "1_2") (pintype "passive"))
    )
    (net (code "85") (name "Net-(IC4-STAT)") (class "Default")
      (node (ref "IC4") (pin "1") (pinfunction "STAT_1") (pintype "output"))
      (node (ref "RN2") (pin "7") (pinfunction "2_7") (pintype "passive"))
      (node (ref "RN2") (pin "8") (pinfunction "2_8") (pintype "passive"))
    )
    (net (code "86") (name "Net-(JP10-Pad1)") (class "Default")
      (node (ref "JP10") (pin "1") (pinfunction "1_1") (pintype "passive"))
      (node (ref "R16") (pin "1") (pinfunction "1_1") (pintype "passive"))
    )
    (net (code "87") (name "Net-(JP11-Pad2)") (class "Default")
      (node (ref "JP11") (pin "2") (pinfunction "2_2") (pintype "passive"))
      (node (ref "PC1") (pin "-") (pinfunction "-_-") (pintype "passive"))
      (node (ref "X4") (pin "3") (pinfunction "3_3") (pintype "passive"))
    )
    (net (code "88") (name "Net-(JP11-Pad3)") (class "Default")
      (node (ref "JP11") (pin "3") (pinfunction "3_3") (pintype "passive"))
      (node (ref "PC2") (pin "-") (pinfunction "-_-") (pintype "passive"))
      (node (ref "X4") (pin "2") (pinfunction "2_2") (pintype "passive"))
    )
    (net (code "89") (name "Net-(Q4-2)") (class "Default")
      (node (ref "C18") (pin "1") (pinfunction "1_1") (pintype "passive"))
      (node (ref "Q4") (pin "3") (pinfunction "2_3") (pintype "passive"))
      (node (ref "R7") (pin "1") (pinfunction "1_1") (pintype "passive"))
      (node (ref "U2") (pin "18") (pinfunction "XTAL1/MCLK_18") (pintype "bidirectional"))
    )
    (net (code "90") (name "Net-(RN2B-1)") (class "Default")
      (node (ref "CHG") (pin "C") (pinfunction "C_C") (pintype "passive"))
      (node (ref "RN2") (pin "1") (pinfunction "1_1") (pintype "passive"))
      (node (ref "RN2") (pin "2") (pinfunction "1_2") (pintype "passive"))
    )
    (net (code "91") (name "Net-(RN3A-2)") (class "Default")
      (node (ref "RN3") (pin "8") (pinfunction "2_8") (pintype "passive"))
      (node (ref "RX") (pin "A") (pinfunction "A_A") (pintype "passive"))
    )
    (net (code "92") (name "Net-(RN3B-2)") (class "Default")
      (node (ref "RN3") (pin "7") (pinfunction "2_7") (pintype "passive"))
      (node (ref "TX") (pin "A") (pinfunction "A_A") (pintype "passive"))
    )
    (net (code "93") (name "Net-(RN3C-2)") (class "Default")
      (node (ref "L") (pin "A") (pinfunction "A_A") (pintype "passive"))
      (node (ref "RN3") (pin "6") (pinfunction "2_6") (pintype "passive"))
    )
    (net (code "94") (name "Net-(RN3D-2)") (class "Default")
      (node (ref "ON") (pin "A") (pinfunction "A_A") (pintype "passive"))
      (node (ref "RN3") (pin "5") (pinfunction "2_5") (pintype "passive"))
    )
    (net (code "95") (name "Net-(RN5A-2)") (class "Default")
      (node (ref "JP4") (pin "1") (pinfunction "1_1") (pintype "passive"))
      (node (ref "RN5") (pin "8") (pinfunction "2_8") (pintype "passive"))
    )
    (net (code "96") (name "Net-(RN5B-2)") (class "Default")
      (node (ref "RN5") (pin "6") (pinfunction "2_6") (pintype "passive"))
      (node (ref "RN5") (pin "7") (pinfunction "2_7") (pintype "passive"))
    )
    (net (code "97") (name "Net-(U2-GPIO2{slash}DCLK)") (class "Default")
      (node (ref "R9") (pin "1") (pinfunction "1_1") (pintype "passive"))
      (node (ref "U2") (pin "10") (pinfunction "GPIO3/SDATA_10") (pintype "bidirectional"))
      (node (ref "U2") (pin "11") (pinfunction "GPIO6_11") (pintype "bidirectional"))
      (node (ref "U2") (pin "12") (pinfunction "GPIO7_12") (pintype "bidirectional"))
      (node (ref "U2") (pin "9") (pinfunction "GPIO2/DCLK_9") (pintype "bidirectional"))
    )
    (net (code "98") (name "Net-(U2-GPIO4{slash}I2S_LROUT)") (class "Default")
      (node (ref "R11") (pin "1") (pinfunction "1_1") (pintype "passive"))
      (node (ref "U2") (pin "36") (pinfunction "GPIO4/I2S_LROUT_36") (pintype "bidirectional"))
    )
    (net (code "99") (name "Net-(U2-GPIO5{slash}I2C_MCLK)") (class "Default")
      (node (ref "R10") (pin "1") (pinfunction "1_1") (pintype "passive"))
      (node (ref "U2") (pin "25") (pinfunction "GPIO5/I2C_MCLK_25") (pintype "bidirectional"))
    )
    (net (code "100") (name "Net-(U2-RCAP)") (class "Default")
      (node (ref "C23") (pin "1") (pinfunction "1_1") (pintype "passive"))
      (node (ref "U2") (pin "44") (pinfunction "RCAP_44") (pintype "bidirectional"))
    )
    (net (code "101") (name "Net-(U2-XTAL2)") (class "Default")
      (node (ref "C19") (pin "1") (pinfunction "1_1") (pintype "passive"))
      (node (ref "Q4") (pin "1") (pinfunction "1_1") (pintype "passive"))
      (node (ref "R7") (pin "2") (pinfunction "2_2") (pintype "passive"))
      (node (ref "U2") (pin "17") (pinfunction "XTAL2_17") (pintype "bidirectional"))
    )
    (net (code "102") (name "UGND") (class "Default")
      (node (ref "C10") (pin "1") (pinfunction "1_1") (pintype "passive"))
      (node (ref "L2") (pin "2") (pinfunction "2_2") (pintype "passive"))
      (node (ref "U1") (pin "5") (pinfunction "UGND_5") (pintype "power_in"))
      (node (ref "X1") (pin "P5") (pinfunction "GND_P5") (pintype "passive"))
    )
    (net (code "103") (name "VIN") (class "Default")
      (node (ref "C1") (pin "1") (pinfunction "1_1") (pintype "passive"))
      (node (ref "C2") (pin "1") (pinfunction "1_1") (pintype "passive"))
      (node (ref "D2") (pin "C") (pinfunction "C_C") (pintype "passive"))
      (node (ref "IC1") (pin "6") (pinfunction "VIN_6") (pintype "bidirectional"))
      (node (ref "L1") (pin "2") (pinfunction "2_2") (pintype "bidirectional"))
      (node (ref "S2") (pin "6") (pinfunction "6_6") (pintype "passive"))
      (node (ref "T1") (pin "2") (pinfunction "S_2") (pintype "passive"))
    )
    (net (code "104") (name "VUSB") (class "Default")
      (node (ref "C17") (pin "2") (pinfunction "2_2") (pintype "passive"))
      (node (ref "C3") (pin "1") (pinfunction "1_1") (pintype "passive"))
      (node (ref "C4") (pin "2") (pinfunction "2_2") (pintype "passive"))
      (node (ref "CHG") (pin "A") (pinfunction "A_A") (pintype "passive"))
      (node (ref "D2") (pin "A") (pinfunction "A_A") (pintype "passive"))
      (node (ref "F1") (pin "2") (pinfunction "2_2") (pintype "bidirectional"))
      (node (ref "IC4") (pin "4") (pinfunction "VIN_4") (pintype "power_in"))
      (node (ref "JP1") (pin "2") (pinfunction "2_2") (pintype "passive"))
      (node (ref "RN6") (pin "4") (pinfunction "1_4") (pintype "passive"))
      (node (ref "T1") (pin "3") (pinfunction "G_3") (pintype "passive"))
      (node (ref "U1") (pin "7") (pinfunction "VBUS_7") (pintype "input"))
    )
    (net (code "105") (name "V_BATT") (class "Default")
      (node (ref "F2") (pin "2") (pinfunction "2_2") (pintype "bidirectional"))
      (node (ref "IC4") (pin "3") (pinfunction "VBAT_3") (pintype "power_in"))
      (node (ref "T1") (pin "1") (pinfunction "D_1") (pintype "passive"))
    )
    (net (code "106") (name "unconnected-(IC7-BP-Pad4)") (class "Default")
      (node (ref "IC7") (pin "4") (pinfunction "BP_4") (pintype "input"))
    )
    (net (code "107") (name "unconnected-(IC8-BP-Pad4)") (class "Default")
      (node (ref "IC8") (pin "4") (pinfunction "BP_4") (pintype "input"))
    )
    (net (code "108") (name "unconnected-(J1-Pad1)") (class "Default")
      (node (ref "J1") (pin "1") (pinfunction "1_1") (pintype "passive"))
    )
    (net (code "109") (name "unconnected-(ORIGIN-TESTP-PadX)") (class "Default")
      (node (ref "ORIGIN") (pin "X") (pinfunction "TESTP_X") (pintype "passive"))
    )
    (net (code "110") (name "unconnected-(RN2C-1-Pad3)") (class "Default")
      (node (ref "RN2") (pin "3") (pinfunction "1_3") (pintype "passive"))
    )
    (net (code "111") (name "unconnected-(RN2C-2-Pad6)") (class "Default")
      (node (ref "RN2") (pin "6") (pinfunction "2_6") (pintype "passive"))
    )
    (net (code "112") (name "unconnected-(RN2D-1-Pad4)") (class "Default")
      (node (ref "RN2") (pin "4") (pinfunction "1_4") (pintype "passive"))
    )
    (net (code "113") (name "unconnected-(RN2D-2-Pad5)") (class "Default")
      (node (ref "RN2") (pin "5") (pinfunction "2_5") (pintype "passive"))
    )
    (net (code "114") (name "unconnected-(RN5D-1-Pad4)") (class "Default")
      (node (ref "RN5") (pin "4") (pinfunction "1_4") (pintype "passive"))
    )
    (net (code "115") (name "unconnected-(RN5D-2-Pad5)") (class "Default")
      (node (ref "RN5") (pin "5") (pinfunction "2_5") (pintype "passive"))
    )
    (net (code "116") (name "unconnected-(RN6C-1-Pad3)") (class "Default")
      (node (ref "RN6") (pin "3") (pinfunction "1_3") (pintype "passive"))
    )
    (net (code "117") (name "unconnected-(U2-GBUF-Pad42)") (class "Default")
      (node (ref "U2") (pin "42") (pinfunction "GBUF_42") (pintype "bidirectional"))
    )
    (net (code "118") (name "unconnected-(U2-LINEIN-Pad48)") (class "Default")
      (node (ref "U2") (pin "48") (pinfunction "LINEIN_48") (pintype "bidirectional"))
    )
    (net (code "119") (name "unconnected-(U2-MICN-Pad2)") (class "Default")
      (node (ref "U2") (pin "2") (pinfunction "MICN_2") (pintype "bidirectional"))
    )
    (net (code "120") (name "unconnected-(U2-MICP-Pad1)") (class "Default")
      (node (ref "U2") (pin "1") (pinfunction "MICP_1") (pintype "bidirectional"))
    )
    (net (code "121") (name "unconnected-(U2-TX-Pad27)") (class "Default")
      (node (ref "U2") (pin "27") (pinfunction "TX_27") (pintype "bidirectional"))
    )
    (net (code "122") (name "unconnected-(U2-VCO-Pad15)") (class "Default")
      (node (ref "U2") (pin "15") (pinfunction "VCO_15") (pintype "bidirectional"))
    )
    (net (code "123") (name "unconnected-(X3-NC-Pad1)") (class "Default")
      (node (ref "X3") (pin "1") (pinfunction "NC_1") (pintype "bidirectional"))
    )
    (net (code "124") (name "unconnected-(X3-PadCD1)") (class "Default")
      (node (ref "X3") (pin "CD1") (pinfunction "CD1_CD1") (pintype "bidirectional"))
    )
    (net (code "125") (name "unconnected-(X3-PadCD2)") (class "Default")
      (node (ref "X3") (pin "CD2") (pinfunction "CD2_CD2") (pintype "bidirectional"))
    )
    (net (code "126") (name "unconnected-(X3-RSV-Pad8)") (class "Default")
      (node (ref "X3") (pin "8") (pinfunction "RSV_8") (pintype "bidirectional"))
    )
  )
)
